# ARboard.net
KiCad netlist of a schematic drawn in EAGLE
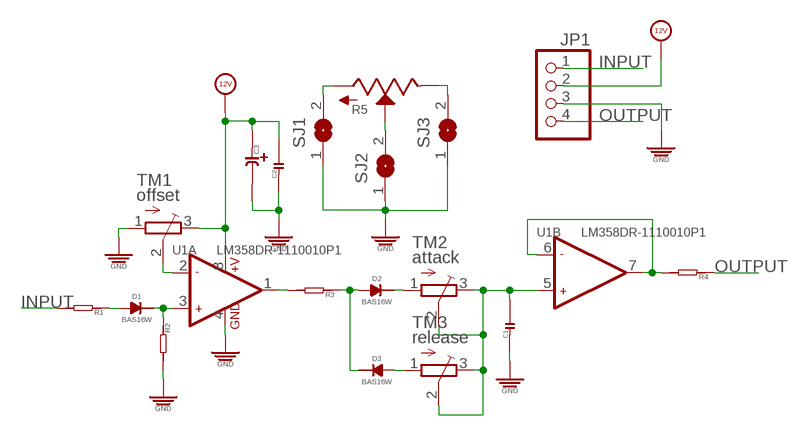
[diagram p0: schematic, sheet 1]

(export (version "E")
  (design (tool "Eeschema 10.0.6"))
  (components
    (comp (ref "C1")
      (value "C-0603")
      (footprint "eagle-import:C0603")
      (libsource (lib "eagle-import") (part "C-0603"))
    )
    (comp (ref "C2")
      (value "C-0603")
      (footprint "eagle-import:C0603")
      (libsource (lib "eagle-import") (part "C-0603"))
    )
    (comp (ref "C3")
      (value "C-POLAR-A")
      (footprint "eagle-import:CASE-A_3216")
      (libsource (lib "eagle-import") (part "C-POLAR-A"))
    )
    (comp (ref "D1")
      (value "BAS16W")
      (footprint "eagle-import:SOT-323")
      (libsource (lib "eagle-import") (part "BAS16W"))
    )
    (comp (ref "D2")
      (value "BAS16W")
      (footprint "eagle-import:SOT-323")
      (libsource (lib "eagle-import") (part "BAS16W"))
    )
    (comp (ref "D3")
      (value "BAS16W")
      (footprint "eagle-import:SOT-323")
      (libsource (lib "eagle-import") (part "BAS16W"))
    )
    (comp (ref "JP1")
      (value "PINHD-1X4")
      (footprint "eagle-import:1X04")
      (libsource (lib "eagle-import") (part "PINHD-1X4"))
    )
    (comp (ref "R1")
      (value "R-0603")
      (footprint "eagle-import:R0603")
      (libsource (lib "eagle-import") (part "R-0603"))
    )
    (comp (ref "R2")
      (value "R-0603")
      (footprint "eagle-import:R0603")
      (libsource (lib "eagle-import") (part "R-0603"))
    )
    (comp (ref "R3")
      (value "R-0603")
      (footprint "eagle-import:R0603")
      (libsource (lib "eagle-import") (part "R-0603"))
    )
    (comp (ref "R4")
      (value "R-0603")
      (footprint "eagle-import:R0603")
      (libsource (lib "eagle-import") (part "R-0603"))
    )
    (comp (ref "R5")
      (value "POTSQUAREHOLE_SMALLKNOB")
      (footprint "eagle-import:ALPS_POT_SQUAREHOLES")
      (libsource (lib "eagle-import") (part "POTSQUAREHOLE_SMALLKNOB"))
    )
    (comp (ref "SJ1") (value "SJ") (footprint "eagle-import:SJ") (libsource (lib "eagle-import") (part "SJ")))
    (comp (ref "SJ2") (value "SJ") (footprint "eagle-import:SJ") (libsource (lib "eagle-import") (part "SJ")))
    (comp (ref "SJ3") (value "SJ") (footprint "eagle-import:SJ") (libsource (lib "eagle-import") (part "SJ")))
    (comp (ref "TM1")
      (value "offset")
      (footprint "eagle-import:TC33X")
      (libsource (lib "eagle-import") (part "TRIMPOTTC33X"))
    )
    (comp (ref "TM2")
      (value "attack")
      (footprint "eagle-import:TC33X")
      (libsource (lib "eagle-import") (part "TRIMPOTTC33X"))
    )
    (comp (ref "TM3")
      (value "release")
      (footprint "eagle-import:TC33X")
      (libsource (lib "eagle-import") (part "TRIMPOTTC33X"))
    )
    (comp (ref "U1")
      (value "LM358DR-1110010P1")
      (footprint "eagle-import:SOIC8")
      (libsource (lib "eagle-import") (part "LM358DR-1110010P1"))
    )
  )
  (nets
    (net (code "1") (name "/INPUT") (class "Default")
      (node (ref "JP1") (pin "1") (pinfunction "1_1") (pintype "passive"))
      (node (ref "R1") (pin "2") (pinfunction "2_2") (pintype "bidirectional"))
    )
    (net (code "2") (name "/OUTPUT") (class "Default")
      (node (ref "JP1") (pin "4") (pinfunction "4_4") (pintype "passive"))
      (node (ref "R4") (pin "1") (pinfunction "1_1") (pintype "bidirectional"))
    )
    (net (code "3") (name "12V") (class "Default")
      (node (ref "C2") (pin "2") (pinfunction "2_2") (pintype "bidirectional"))
      (node (ref "C3") (pin "+") (pinfunction "1_+") (pintype "bidirectional"))
      (node (ref "JP1") (pin "2") (pinfunction "2_2") (pintype "passive"))
      (node (ref "TM1") (pin "3") (pinfunction "E_3") (pintype "passive"))
      (node (ref "U1") (pin "8") (pinfunction "+V_8") (pintype "power_in"))
    )
    (net (code "4") (name "GND") (class "Default")
      (node (ref "C1") (pin "1") (pinfunction "1_1") (pintype "bidirectional"))
      (node (ref "C2") (pin "1") (pinfunction "1_1") (pintype "bidirectional"))
      (node (ref "C3") (pin "-") (pinfunction "2_-") (pintype "bidirectional"))
      (node (ref "JP1") (pin "3") (pinfunction "3_3") (pintype "passive"))
      (node (ref "R2") (pin "2") (pinfunction "2_2") (pintype "bidirectional"))
      (node (ref "SJ1") (pin "1") (pinfunction "1_1") (pintype "passive"))
      (node (ref "SJ2") (pin "1") (pinfunction "1_1") (pintype "passive"))
      (node (ref "SJ3") (pin "1") (pinfunction "1_1") (pintype "passive"))
      (node (ref "TM1") (pin "1") (pinfunction "A_1") (pintype "passive"))
      (node (ref "U1") (pin "4") (pinfunction "GND_4") (pintype "power_in"))
    )
    (net (code "5") (name "Net-(D1-PadANODE)") (class "Default")
      (node (ref "D1") (pin "ANODE") (pinfunction "ANODE_ANODE") (pintype "bidirectional"))
      (node (ref "R1") (pin "1") (pinfunction "1_1") (pintype "bidirectional"))
    )
    (net (code "6") (name "Net-(D2-PadANODE)") (class "Default")
      (node (ref "D2") (pin "ANODE") (pinfunction "ANODE_ANODE") (pintype "bidirectional"))
      (node (ref "D3") (pin "CATHODE") (pinfunction "CATHODE_CATHODE") (pintype "bidirectional"))
      (node (ref "R3") (pin "1") (pinfunction "1_1") (pintype "bidirectional"))
    )
    (net (code "7") (name "Net-(R5-A)") (class "Default")
      (node (ref "R5") (pin "P$3") (pinfunction "A_P$3") (pintype "passive"))
      (node (ref "SJ1") (pin "2") (pinfunction "2_2") (pintype "passive"))
    )
    (net (code "8") (name "Net-(R5-E)") (class "Default")
      (node (ref "R5") (pin "P$1") (pinfunction "E_P$1") (pintype "passive"))
      (node (ref "SJ3") (pin "2") (pinfunction "2_2") (pintype "passive"))
    )
    (net (code "9") (name "Net-(R5-S)") (class "Default")
      (node (ref "R5") (pin "P$2") (pinfunction "S_P$2") (pintype "passive"))
      (node (ref "SJ2") (pin "2") (pinfunction "2_2") (pintype "passive"))
    )
    (net (code "10") (name "Net-(TM1-S)") (class "Default")
      (node (ref "TM1") (pin "2") (pinfunction "S_2") (pintype "passive"))
      (node (ref "U1") (pin "2") (pinfunction "-IN1_2") (pintype "input"))
    )
    (net (code "11") (name "Net-(TM2-A)") (class "Default")
      (node (ref "D2") (pin "CATHODE") (pinfunction "CATHODE_CATHODE") (pintype "bidirectional"))
      (node (ref "TM2") (pin "1") (pinfunction "A_1") (pintype "passive"))
    )
    (net (code "12") (name "Net-(TM2-E)") (class "Default")
      (node (ref "C1") (pin "2") (pinfunction "2_2") (pintype "bidirectional"))
      (node (ref "TM2") (pin "2") (pinfunction "S_2") (pintype "passive"))
      (node (ref "TM2") (pin "3") (pinfunction "E_3") (pintype "passive"))
      (node (ref "TM3") (pin "2") (pinfunction "S_2") (pintype "passive"))
      (node (ref "TM3") (pin "3") (pinfunction "E_3") (pintype "passive"))
      (node (ref "U1") (pin "5") (pinfunction "+IN2_5") (pintype "input"))
    )
    (net (code "13") (name "Net-(TM3-A)") (class "Default")
      (node (ref "D3") (pin "ANODE") (pinfunction "ANODE_ANODE") (pintype "bidirectional"))
      (node (ref "TM3") (pin "1") (pinfunction "A_1") (pintype "passive"))
    )
    (net (code "14") (name "Net-(U1A-+IN1)") (class "Default")
      (node (ref "D1") (pin "CATHODE") (pinfunction "CATHODE_CATHODE") (pintype "bidirectional"))
      (node (ref "R2") (pin "1") (pinfunction "1_1") (pintype "bidirectional"))
      (node (ref "U1") (pin "3") (pinfunction "+IN1_3") (pintype "input"))
    )
    (net (code "15") (name "Net-(U1A-OUT1)") (class "Default")
      (node (ref "R3") (pin "2") (pinfunction "2_2") (pintype "bidirectional"))
      (node (ref "U1") (pin "1") (pinfunction "OUT1_1") (pintype "output"))
    )
    (net (code "16") (name "Net-(U1B--IN2)") (class "Default")
      (node (ref "R4") (pin "2") (pinfunction "2_2") (pintype "bidirectional"))
      (node (ref "U1") (pin "6") (pinfunction "-IN2_6") (pintype "input"))
      (node (ref "U1") (pin "7") (pinfunction "OUT2_7") (pintype "output"))
    )
  )
)
